# Lantern_Vent.net
KiCad netlist of a schematic drawn in EAGLE
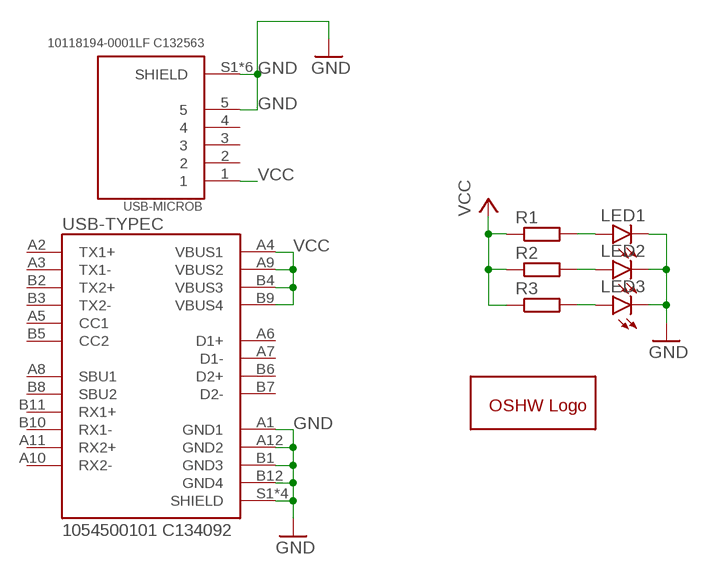
[diagram p0: schematic, sheet 1]

(export (version "E")
  (design (tool "Eeschema 10.0.6"))
  (components
    (comp (ref "GOLD_ORB_SM1")
      (value "OSHWLOGOLOGO5MM")
      (footprint "eagle-import:OSHW_5MM")
      (libsource (lib "eagle-import") (part "OSHWLOGOLOGO5MM"))
    )
    (comp (ref "LED1")
      (value "LEDCHIP-LED0805")
      (footprint "eagle-import:CHIP-LED0805")
      (libsource (lib "eagle-import") (part "LEDCHIP-LED0805"))
    )
    (comp (ref "LED2")
      (value "LEDCHIP-LED0805")
      (footprint "eagle-import:CHIP-LED0805")
      (libsource (lib "eagle-import") (part "LEDCHIP-LED0805"))
    )
    (comp (ref "LED3")
      (value "LEDCHIP-LED0805")
      (footprint "eagle-import:CHIP-LED0805")
      (libsource (lib "eagle-import") (part "LEDCHIP-LED0805"))
    )
    (comp (ref "R1")
      (value "R-EU_R0805")
      (footprint "eagle-import:R0805")
      (libsource (lib "eagle-import") (part "R-EU_R0805"))
    )
    (comp (ref "R2")
      (value "R-EU_R0805")
      (footprint "eagle-import:R0805")
      (libsource (lib "eagle-import") (part "R-EU_R0805"))
    )
    (comp (ref "R3")
      (value "R-EU_R0805")
      (footprint "eagle-import:R0805")
      (libsource (lib "eagle-import") (part "R-EU_R0805"))
    )
    (comp (ref "USB-MICROB")
      (value "10118194-0001LF C132563")
      (footprint "eagle-import:AMPHENOL_10118194-0001LF")
      (fields (field (name "MF") "Amphenol ICC (FCI)") (field (name "MP") "10118194-0001LF"))
      (libsource (lib "eagle-import") (part "10118194-0001LF"))
    )
    (comp (ref "USB-TYPEC")
      (value "1054500101 C134092")
      (footprint "eagle-import:MOLEX_105450-0101")
      (fields (field (name "MF") "Molex") (field (name "MP") "1054500101"))
      (libsource (lib "eagle-import") (part "105450-0101"))
    )
  )
  (nets
    (net (code "1") (name "GND") (class "Default")
      (node (ref "LED1") (pin "C") (pinfunction "C_C") (pintype "passive"))
      (node (ref "LED2") (pin "C") (pinfunction "C_C") (pintype "passive"))
      (node (ref "LED3") (pin "C") (pinfunction "C_C") (pintype "passive"))
      (node (ref "USB-MICROB") (pin "5") (pinfunction "5_5") (pintype "passive"))
      (node (ref "USB-MICROB") (pin "S1") (pinfunction "SHIELD_S1") (pintype "passive"))
      (node (ref "USB-MICROB") (pin "S2") (pinfunction "SHIELD_S2") (pintype "passive"))
      (node (ref "USB-MICROB") (pin "S3") (pinfunction "SHIELD_S3") (pintype "passive"))
      (node (ref "USB-MICROB") (pin "S4") (pinfunction "SHIELD_S4") (pintype "passive"))
      (node (ref "USB-MICROB") (pin "S5") (pinfunction "SHIELD_S5") (pintype "passive"))
      (node (ref "USB-MICROB") (pin "S6") (pinfunction "SHIELD_S6") (pintype "passive"))
      (node (ref "USB-TYPEC") (pin "A1") (pinfunction "GND1_A1") (pintype "passive"))
      (node (ref "USB-TYPEC") (pin "A12") (pinfunction "GND2_A12") (pintype "passive"))
      (node (ref "USB-TYPEC") (pin "B1") (pinfunction "GND3_B1") (pintype "passive"))
      (node (ref "USB-TYPEC") (pin "B12") (pinfunction "GND4_B12") (pintype "passive"))
      (node (ref "USB-TYPEC") (pin "S1") (pinfunction "SHIELD_S1") (pintype "passive"))
      (node (ref "USB-TYPEC") (pin "S2") (pinfunction "SHIELD_S2") (pintype "passive"))
      (node (ref "USB-TYPEC") (pin "S3") (pinfunction "SHIELD_S3") (pintype "passive"))
      (node (ref "USB-TYPEC") (pin "S4") (pinfunction "SHIELD_S4") (pintype "passive"))
    )
    (net (code "2") (name "Net-(LED1-PadA)") (class "Default")
      (node (ref "LED1") (pin "A") (pinfunction "A_A") (pintype "passive"))
      (node (ref "R1") (pin "2") (pinfunction "2_2") (pintype "passive"))
    )
    (net (code "3") (name "Net-(LED2-PadA)") (class "Default")
      (node (ref "LED2") (pin "A") (pinfunction "A_A") (pintype "passive"))
      (node (ref "R2") (pin "2") (pinfunction "2_2") (pintype "passive"))
    )
    (net (code "4") (name "Net-(LED3-PadA)") (class "Default")
      (node (ref "LED3") (pin "A") (pinfunction "A_A") (pintype "passive"))
      (node (ref "R3") (pin "2") (pinfunction "2_2") (pintype "passive"))
    )
    (net (code "5") (name "VCC") (class "Default")
      (node (ref "R1") (pin "1") (pinfunction "1_1") (pintype "passive"))
      (node (ref "R2") (pin "1") (pinfunction "1_1") (pintype "passive"))
      (node (ref "R3") (pin "1") (pinfunction "1_1") (pintype "passive"))
      (node (ref "USB-MICROB") (pin "1") (pinfunction "1_1") (pintype "passive"))
      (node (ref "USB-TYPEC") (pin "A4") (pinfunction "VBUS1_A4") (pintype "passive"))
      (node (ref "USB-TYPEC") (pin "A9") (pinfunction "VBUS2_A9") (pintype "passive"))
      (node (ref "USB-TYPEC") (pin "B4") (pinfunction "VBUS3_B4") (pintype "passive"))
      (node (ref "USB-TYPEC") (pin "B9") (pinfunction "VBUS4_B9") (pintype "passive"))
    )
    (net (code "6") (name "unconnected-(USB-MICROB-Pad2)") (class "Default")
      (node (ref "USB-MICROB") (pin "2") (pinfunction "2_2") (pintype "passive"))
    )
    (net (code "7") (name "unconnected-(USB-MICROB-Pad3)") (class "Default")
      (node (ref "USB-MICROB") (pin "3") (pinfunction "3_3") (pintype "passive"))
    )
    (net (code "8") (name "unconnected-(USB-MICROB-Pad4)") (class "Default")
      (node (ref "USB-MICROB") (pin "4") (pinfunction "4_4") (pintype "passive"))
    )
    (net (code "9") (name "unconnected-(USB-TYPEC-CC1-PadA5)") (class "Default")
      (node (ref "USB-TYPEC") (pin "A5") (pinfunction "CC1_A5") (pintype "passive"))
    )
    (net (code "10") (name "unconnected-(USB-TYPEC-CC2-PadB5)") (class "Default")
      (node (ref "USB-TYPEC") (pin "B5") (pinfunction "CC2_B5") (pintype "passive"))
    )
    (net (code "11") (name "unconnected-(USB-TYPEC-D1+-PadA6)") (class "Default")
      (node (ref "USB-TYPEC") (pin "A6") (pinfunction "D1+_A6") (pintype "passive"))
    )
    (net (code "12") (name "unconnected-(USB-TYPEC-D1--PadA7)") (class "Default")
      (node (ref "USB-TYPEC") (pin "A7") (pinfunction "D1-_A7") (pintype "passive"))
    )
    (net (code "13") (name "unconnected-(USB-TYPEC-D2+-PadB6)") (class "Default")
      (node (ref "USB-TYPEC") (pin "B6") (pinfunction "D2+_B6") (pintype "passive"))
    )
    (net (code "14") (name "unconnected-(USB-TYPEC-D2--PadB7)") (class "Default")
      (node (ref "USB-TYPEC") (pin "B7") (pinfunction "D2-_B7") (pintype "passive"))
    )
    (net (code "15") (name "unconnected-(USB-TYPEC-RX1+-PadB11)") (class "Default")
      (node (ref "USB-TYPEC") (pin "B11") (pinfunction "RX1+_B11") (pintype "passive"))
    )
    (net (code "16") (name "unconnected-(USB-TYPEC-RX1--PadB10)") (class "Default")
      (node (ref "USB-TYPEC") (pin "B10") (pinfunction "RX1-_B10") (pintype "passive"))
    )
    (net (code "17") (name "unconnected-(USB-TYPEC-RX2+-PadA11)") (class "Default")
      (node (ref "USB-TYPEC") (pin "A11") (pinfunction "RX2+_A11") (pintype "passive"))
    )
    (net (code "18") (name "unconnected-(USB-TYPEC-RX2--PadA10)") (class "Default")
      (node (ref "USB-TYPEC") (pin "A10") (pinfunction "RX2-_A10") (pintype "passive"))
    )
    (net (code "19") (name "unconnected-(USB-TYPEC-SBU1-PadA8)") (class "Default")
      (node (ref "USB-TYPEC") (pin "A8") (pinfunction "SBU1_A8") (pintype "passive"))
    )
    (net (code "20") (name "unconnected-(USB-TYPEC-SBU2-PadB8)") (class "Default")
      (node (ref "USB-TYPEC") (pin "B8") (pinfunction "SBU2_B8") (pintype "passive"))
    )
    (net (code "21") (name "unconnected-(USB-TYPEC-TX1+-PadA2)") (class "Default")
      (node (ref "USB-TYPEC") (pin "A2") (pinfunction "TX1+_A2") (pintype "passive"))
    )
    (net (code "22") (name "unconnected-(USB-TYPEC-TX1--PadA3)") (class "Default")
      (node (ref "USB-TYPEC") (pin "A3") (pinfunction "TX1-_A3") (pintype "passive"))
    )
    (net (code "23") (name "unconnected-(USB-TYPEC-TX2+-PadB2)") (class "Default")
      (node (ref "USB-TYPEC") (pin "B2") (pinfunction "TX2+_B2") (pintype "passive"))
    )
    (net (code "24") (name "unconnected-(USB-TYPEC-TX2--PadB3)") (class "Default")
      (node (ref "USB-TYPEC") (pin "B3") (pinfunction "TX2-_B3") (pintype "passive"))
    )
  )
)
